# Mini-RS485_RJ45-GW-v01.net
KiCad netlist of a schematic drawn in EAGLE
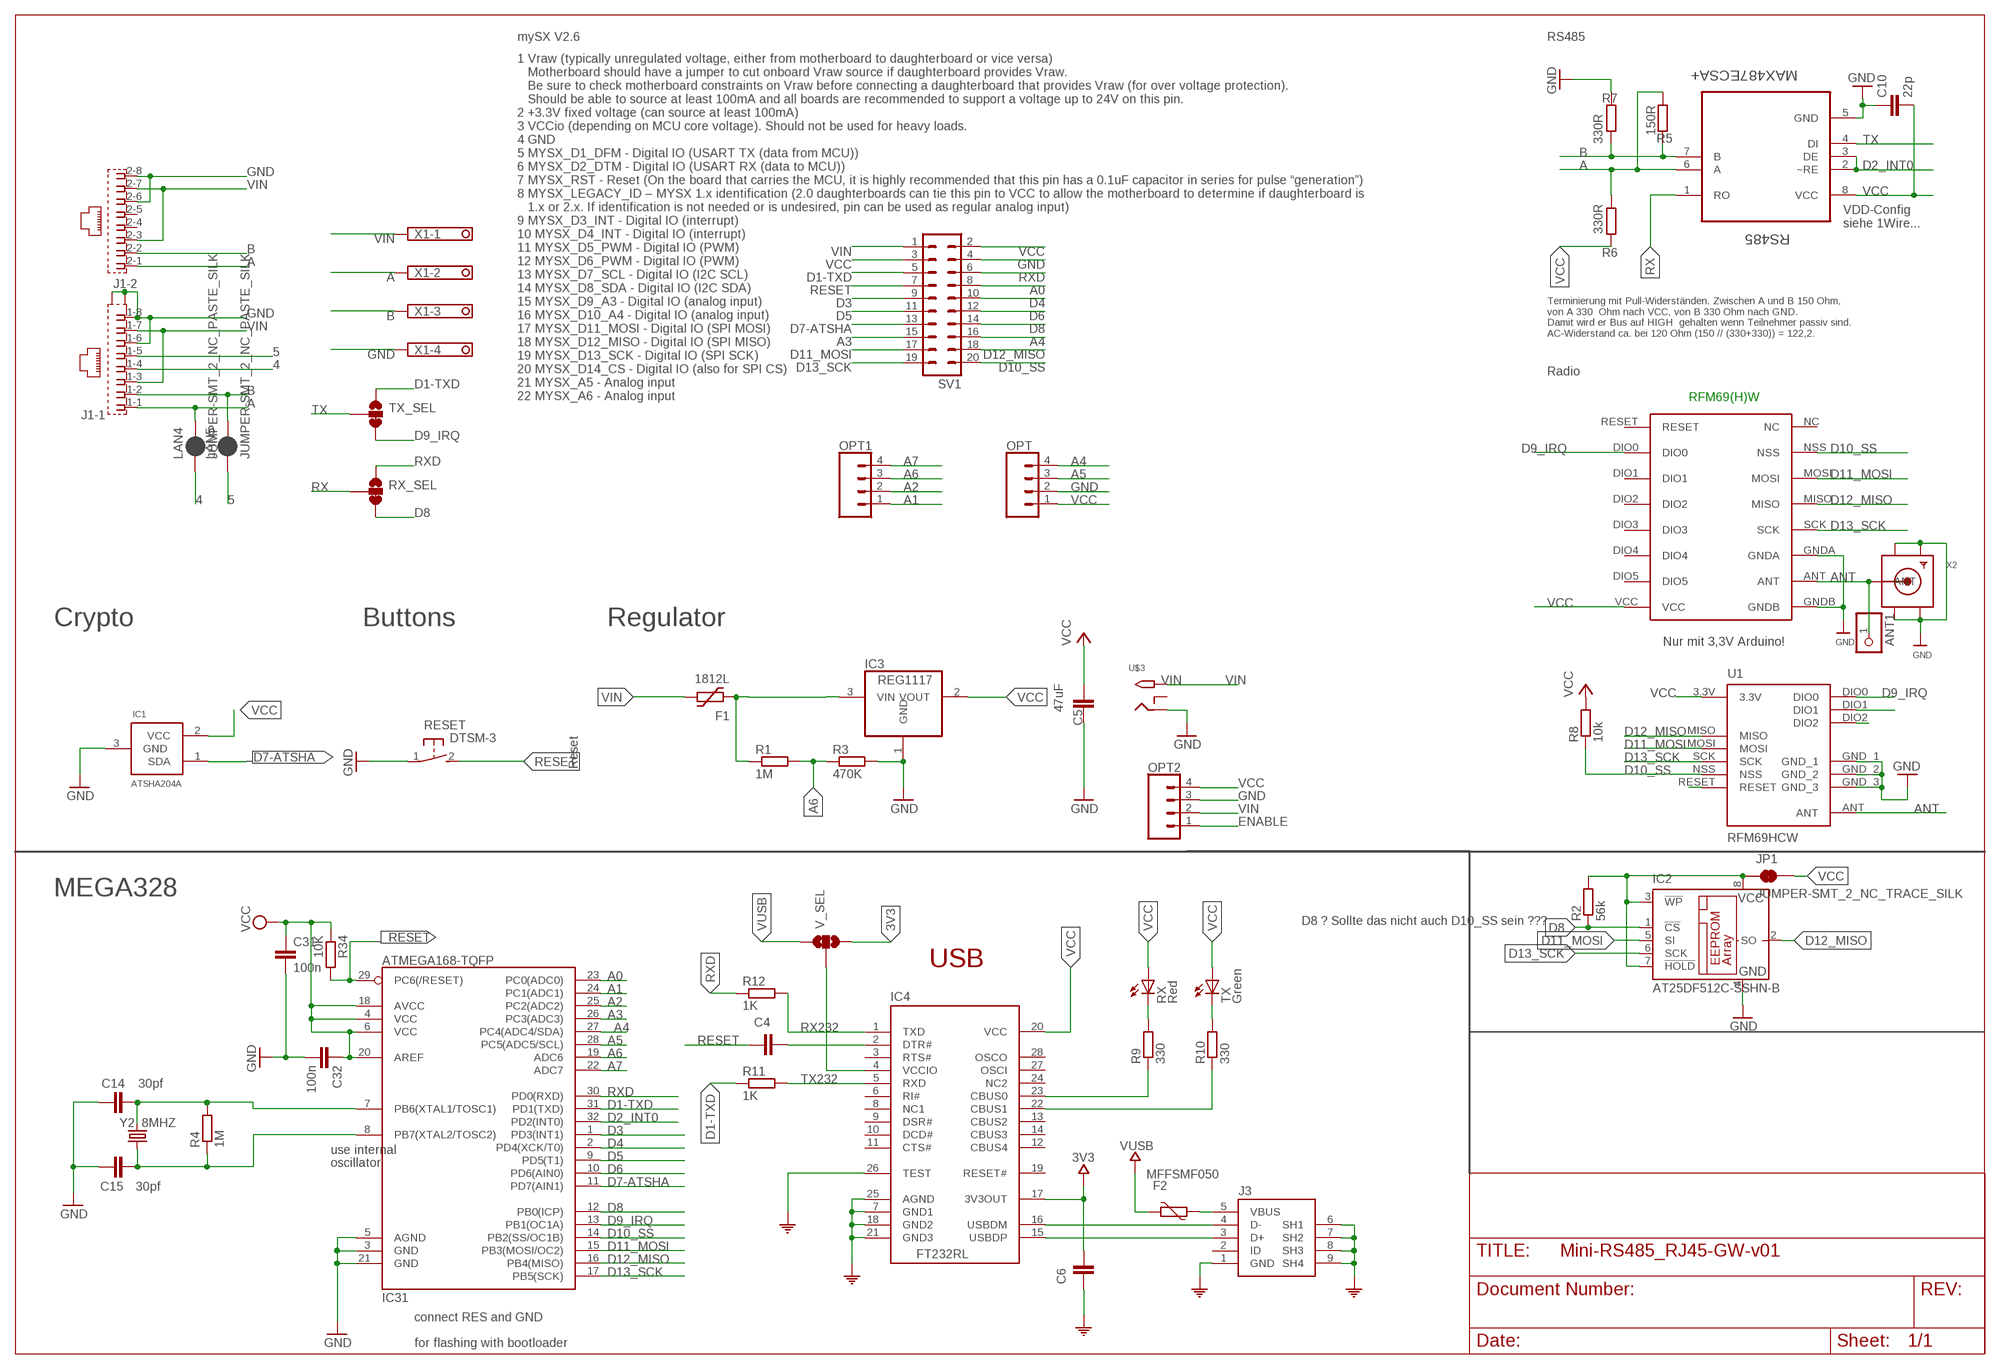
[diagram p0: schematic, sheet 1]

(export (version "E")
  (design (tool "Eeschema 10.0.6"))
  (components
    (comp (ref "ANT1")
      (value "PINHD-1X1")
      (footprint "eagle-import:1X01")
      (libsource (lib "eagle-import") (part "PINHD-1X1"))
    )
    (comp (ref "C4")
      (value "100nF")
      (footprint "eagle-import:C0805")
      (libsource (lib "eagle-import") (part "resistor_348_C-EUC0805"))
    )
    (comp (ref "C5")
      (value "47uF")
      (footprint "eagle-import:C1210")
      (libsource (lib "eagle-import") (part "C-EUC1210"))
    )
    (comp (ref "C6")
      (value "100nF")
      (footprint "eagle-import:C0805")
      (libsource (lib "eagle-import") (part "resistor_348_C-EUC0805"))
    )
    (comp (ref "C10")
      (value "22p")
      (footprint "eagle-import:C0805")
      (libsource (lib "eagle-import") (part "C-EUC0805"))
    )
    (comp (ref "C14")
      (value "30pf")
      (footprint "eagle-import:0805")
      (libsource (lib "eagle-import") (part "CAP0805"))
    )
    (comp (ref "C15")
      (value "30pf")
      (footprint "eagle-import:0805")
      (libsource (lib "eagle-import") (part "CAP0805"))
    )
    (comp (ref "C31")
      (value "100n")
      (footprint "eagle-import:C0805")
      (libsource (lib "eagle-import") (part "C-EUC0805"))
    )
    (comp (ref "C32")
      (value "100n")
      (footprint "eagle-import:C0805")
      (libsource (lib "eagle-import") (part "C-EUC0805"))
    )
    (comp (ref "F1")
      (value "1812L")
      (footprint "eagle-import:1812L")
      (libsource (lib "eagle-import") (part "1812L"))
    )
    (comp (ref "F2")
      (value "MFFSMF050")
      (footprint "eagle-import:0603-1608X90N")
      (fields (field (name "MANUFACTURER") "Bourns Inc "))
      (libsource (lib "eagle-import") (part "PTC"))
    )
    (comp (ref "IC1")
      (value "ATSHA204A")
      (footprint "eagle-import:SOT23")
      (libsource (lib "eagle-import") (part "ATSHA204A"))
    )
    (comp (ref "IC2")
      (value "AT25DF512C-SSHN-B")
      (footprint "eagle-import:SO-08")
      (fields (field (name "MF") "MICROCHIP") (field (name "MPN") "25AA080/SN"))
      (libsource (lib "eagle-import") (part "25SNAA080"))
    )
    (comp (ref "IC3")
      (value "REG1117")
      (footprint "eagle-import:SOT223")
      (libsource (lib "eagle-import") (part "REG1117"))
    )
    (comp (ref "IC4")
      (value "FT232RL")
      (footprint "eagle-import:SSOP28")
      (libsource (lib "eagle-import") (part "0226_FT232RL"))
    )
    (comp (ref "IC31")
      (value "ATMEGA168-TQFP")
      (footprint "eagle-import:TQFP32-08")
      (libsource (lib "eagle-import") (part "ATMEGA168-TQFP"))
    )
    (comp (ref "J1")
      (value "RJ45_2X_NARROW_SHILDPINS")
      (footprint "eagle-import:RJ45_2X_NARROW_SHILDPINS")
      (libsource (lib "eagle-import") (part "RJ45_2X_NARROW_SHILDPINS"))
    )
    (comp (ref "J3")
      (value "0219_14850")
      (footprint "eagle-import:USB-MINI-B_2")
      (fields (field (name "PART_NUMBER") "14850"))
      (libsource (lib "eagle-import") (part "0219_14850"))
    )
    (comp (ref "JP1")
      (value "JUMPER-SMT_2_NC_TRACE_SILK")
      (footprint "eagle-import:SMT-JUMPER_2_NC_TRACE_SILK")
      (libsource (lib "eagle-import") (part "JUMPER-SMT_2_NC_TRACE_SILK"))
    )
    (comp (ref "LAN4")
      (value "JUMPER-SMT_2_NC_PASTE_SILK")
      (footprint "eagle-import:SMT-JUMPER_2_NC_PASTE_SILK")
      (libsource (lib "eagle-import") (part "JUMPER-SMT_2_NC_PASTE_SILK"))
    )
    (comp (ref "LAN5")
      (value "JUMPER-SMT_2_NC_PASTE_SILK")
      (footprint "eagle-import:SMT-JUMPER_2_NC_PASTE_SILK")
      (libsource (lib "eagle-import") (part "JUMPER-SMT_2_NC_PASTE_SILK"))
    )
    (comp (ref "OPT")
      (value "CONN_04")
      (footprint "eagle-import:1X04")
      (libsource (lib "eagle-import") (part "CONN_04"))
    )
    (comp (ref "OPT1")
      (value "CONN_04")
      (footprint "eagle-import:1X04")
      (libsource (lib "eagle-import") (part "CONN_04"))
    )
    (comp (ref "OPT2")
      (value "CONN_04")
      (footprint "eagle-import:1X04")
      (libsource (lib "eagle-import") (part "CONN_04"))
    )
    (comp (ref "R1")
      (value "1M")
      (footprint "eagle-import:M0805")
      (libsource (lib "eagle-import") (part "R-EU_M0805"))
    )
    (comp (ref "R2")
      (value "56k")
      (footprint "eagle-import:M0805")
      (libsource (lib "eagle-import") (part "resistor_R-EU_M0805"))
    )
    (comp (ref "R3")
      (value "470K")
      (footprint "eagle-import:R0805")
      (libsource (lib "eagle-import") (part "R-EU_R0805"))
    )
    (comp (ref "R4")
      (value "1M")
      (footprint "eagle-import:M0805")
      (libsource (lib "eagle-import") (part "R-EU_M0805"))
    )
    (comp (ref "R5")
      (value "150R")
      (footprint "eagle-import:R0805")
      (libsource (lib "eagle-import") (part "R-EU_R0805"))
    )
    (comp (ref "R6")
      (value "330R")
      (footprint "eagle-import:R0805")
      (libsource (lib "eagle-import") (part "R-EU_R0805"))
    )
    (comp (ref "R7")
      (value "330R")
      (footprint "eagle-import:R0805")
      (libsource (lib "eagle-import") (part "R-EU_R0805"))
    )
    (comp (ref "R8")
      (value "10k")
      (footprint "eagle-import:M0805")
      (libsource (lib "eagle-import") (part "R-EU_M0805"))
    )
    (comp (ref "R9")
      (value "330")
      (footprint "eagle-import:R0805")
      (libsource (lib "eagle-import") (part "resistor_348_R-EU_R0805"))
    )
    (comp (ref "R10")
      (value "330")
      (footprint "eagle-import:R0805")
      (libsource (lib "eagle-import") (part "resistor_348_R-EU_R0805"))
    )
    (comp (ref "R11")
      (value "1K")
      (footprint "eagle-import:R0805")
      (libsource (lib "eagle-import") (part "resistor_348_R-EU_R0805"))
    )
    (comp (ref "R12")
      (value "1K")
      (footprint "eagle-import:R0805")
      (libsource (lib "eagle-import") (part "resistor_348_R-EU_R0805"))
    )
    (comp (ref "R34")
      (value "10K")
      (footprint "eagle-import:R0805")
      (libsource (lib "eagle-import") (part "R-EU_R0805"))
    )
    (comp (ref "RESET")
      (value "DTSM-3")
      (footprint "eagle-import:DTSM-3")
      (libsource (lib "eagle-import") (part "DTSM-3"))
    )
    (comp (ref "RFM69W")
      (value "RFM69HW")
      (footprint "eagle-import:RFM")
      (libsource (lib "eagle-import") (part "RFM69HW"))
    )
    (comp (ref "RS485")
      (value "MAX487ECSA+")
      (footprint "eagle-import:SOIC127P600X175-8N")
      (libsource (lib "eagle-import") (part "MAX487ECSA+"))
    )
    (comp (ref "RX")
      (value "Red")
      (footprint "eagle-import:CHIPLED_0805")
      (fields (field (name "PART_NUMBER") "KTP-2012SURCK"))
      (libsource (lib "eagle-import") (part "0181_KTP-2012SURCK"))
    )
    (comp (ref "RX_SEL")
      (value "JUMPER-SMT_3_1-NC_TRACE_SILK")
      (footprint "eagle-import:SMT-JUMPER_3_1-NC_TRACE_SILK")
      (libsource (lib "eagle-import") (part "JUMPER-SMT_3_1-NC_TRACE_SILK"))
    )
    (comp (ref "SV1")
      (value "MA10-2")
      (footprint "eagle-import:MA10-2")
      (libsource (lib "eagle-import") (part "MA10-2"))
    )
    (comp (ref "TX")
      (value "Green")
      (footprint "eagle-import:CHIPLED_0805")
      (fields (field (name "PART_NUMBER") "KPT-2012SGC"))
      (libsource (lib "eagle-import") (part "0043_KPT-2012SGC"))
    )
    (comp (ref "TX_SEL")
      (value "JUMPER-SMT_3_1-NC_TRACE_SILK")
      (footprint "eagle-import:SMT-JUMPER_3_1-NC_TRACE_SILK")
      (libsource (lib "eagle-import") (part "JUMPER-SMT_3_1-NC_TRACE_SILK"))
    )
    (comp (ref "U$3")
      (value "2.1MMJACKTHM")
      (footprint "eagle-import:PJ-102A")
      (libsource (lib "eagle-import") (part "2.1MMJACKTHM"))
    )
    (comp (ref "U1")
      (value "RFM69HCW")
      (footprint "eagle-import:RFM69HCW-XXXS2")
      (libsource (lib "eagle-import") (part "RFM69HCW"))
    )
    (comp (ref "V_SEL")
      (value "JUMPER-SMT_3_NO_SILK")
      (footprint "eagle-import:SMT-JUMPER_3_NO_SILK")
      (libsource (lib "eagle-import") (part "JUMPER-SMT_3_NO_SILK"))
    )
    (comp (ref "X1")
      (value "1751264")
      (footprint "eagle-import:1751264")
      (libsource (lib "eagle-import") (part "1751264"))
    )
    (comp (ref "X2")
      (value "SMACONNECTOR_EDGE")
      (footprint "eagle-import:SMA_EDGELAUNCH")
      (libsource (lib "eagle-import") (part "SMACONNECTOR_EDGE"))
    )
    (comp (ref "Y2")
      (value "8MHZ")
      (footprint "eagle-import:CRYSTAL-TXC-7A")
      (libsource (lib "eagle-import") (part "CRYSTALTXC-7A"))
    )
  )
  (nets
    (net (code "1") (name "/4") (class "Default")
      (node (ref "J1") (pin "1-4") (pinfunction "4_1-4") (pintype "passive"))
      (node (ref "LAN4") (pin "1") (pinfunction "1_1") (pintype "passive"))
    )
    (net (code "2") (name "/5") (class "Default")
      (node (ref "J1") (pin "1-5") (pinfunction "5_1-5") (pintype "passive"))
      (node (ref "LAN5") (pin "1") (pinfunction "1_1") (pintype "passive"))
    )
    (net (code "3") (name "/A") (class "Default")
      (node (ref "J1") (pin "1-1") (pinfunction "1_1-1") (pintype "passive"))
      (node (ref "J1") (pin "2-1") (pinfunction "1_2-1") (pintype "passive"))
      (node (ref "LAN4") (pin "2") (pinfunction "2_2") (pintype "passive"))
      (node (ref "R5") (pin "1") (pinfunction "1_1") (pintype "passive"))
      (node (ref "R6") (pin "2") (pinfunction "2_2") (pintype "passive"))
      (node (ref "RS485") (pin "6") (pinfunction "A_6") (pintype "bidirectional"))
      (node (ref "X1") (pin "2") (pinfunction "K_2") (pintype "passive"))
    )
    (net (code "4") (name "/A0") (class "Default")
      (node (ref "IC31") (pin "23") (pinfunction "PC0(ADC0)_23") (pintype "bidirectional"))
      (node (ref "SV1") (pin "8") (pinfunction "8_8") (pintype "passive"))
    )
    (net (code "5") (name "/A1") (class "Default")
      (node (ref "IC31") (pin "24") (pinfunction "PC1(ADC1)_24") (pintype "bidirectional"))
      (node (ref "OPT1") (pin "1") (pinfunction "1_1") (pintype "passive"))
    )
    (net (code "6") (name "/A2") (class "Default")
      (node (ref "IC31") (pin "25") (pinfunction "PC2(ADC2)_25") (pintype "bidirectional"))
      (node (ref "OPT1") (pin "2") (pinfunction "2_2") (pintype "passive"))
    )
    (net (code "7") (name "/A3") (class "Default")
      (node (ref "IC31") (pin "26") (pinfunction "PC3(ADC3)_26") (pintype "bidirectional"))
      (node (ref "SV1") (pin "15") (pinfunction "15_15") (pintype "passive"))
    )
    (net (code "8") (name "/A4") (class "Default")
      (node (ref "IC31") (pin "27") (pinfunction "PC4(ADC4/SDA)_27") (pintype "bidirectional"))
      (node (ref "OPT") (pin "4") (pinfunction "4_4") (pintype "passive"))
      (node (ref "SV1") (pin "16") (pinfunction "16_16") (pintype "passive"))
    )
    (net (code "9") (name "/A5") (class "Default")
      (node (ref "IC31") (pin "28") (pinfunction "PC5(ADC5/SCL)_28") (pintype "bidirectional"))
      (node (ref "OPT") (pin "3") (pinfunction "3_3") (pintype "passive"))
    )
    (net (code "10") (name "/A7") (class "Default")
      (node (ref "IC31") (pin "22") (pinfunction "ADC7_22") (pintype "bidirectional"))
      (node (ref "OPT1") (pin "4") (pinfunction "4_4") (pintype "passive"))
    )
    (net (code "11") (name "/ANT") (class "Default")
      (node (ref "ANT1") (pin "1") (pinfunction "1_1") (pintype "passive"))
      (node (ref "RFM69W") (pin "ANT") (pinfunction "ANT_ANT") (pintype "bidirectional"))
      (node (ref "U1") (pin "ANT") (pinfunction "ANT_ANT") (pintype "passive"))
      (node (ref "X2") (pin "P") (pinfunction "ANT_P") (pintype "bidirectional"))
    )
    (net (code "12") (name "/B") (class "Default")
      (node (ref "J1") (pin "1-2") (pinfunction "2_1-2") (pintype "passive"))
      (node (ref "J1") (pin "2-2") (pinfunction "2_2-2") (pintype "passive"))
      (node (ref "LAN5") (pin "2") (pinfunction "2_2") (pintype "passive"))
      (node (ref "R5") (pin "2") (pinfunction "2_2") (pintype "passive"))
      (node (ref "R7") (pin "1") (pinfunction "1_1") (pintype "passive"))
      (node (ref "RS485") (pin "7") (pinfunction "B_7") (pintype "bidirectional"))
      (node (ref "X1") (pin "3") (pinfunction "K_3") (pintype "passive"))
    )
    (net (code "13") (name "/D2_INT0") (class "Default")
      (node (ref "IC31") (pin "32") (pinfunction "PD2(INT0)_32") (pintype "bidirectional"))
      (node (ref "RS485") (pin "2") (pinfunction "~{RE}_2") (pintype "input"))
      (node (ref "RS485") (pin "3") (pinfunction "DE_3") (pintype "input"))
    )
    (net (code "14") (name "/D3") (class "Default")
      (node (ref "IC31") (pin "1") (pinfunction "PD3(INT1)_1") (pintype "bidirectional"))
      (node (ref "SV1") (pin "9") (pinfunction "9_9") (pintype "passive"))
    )
    (net (code "15") (name "/D4") (class "Default")
      (node (ref "IC31") (pin "2") (pinfunction "PD4(XCK/T0)_2") (pintype "bidirectional"))
      (node (ref "SV1") (pin "10") (pinfunction "10_10") (pintype "passive"))
    )
    (net (code "16") (name "/D5") (class "Default")
      (node (ref "IC31") (pin "9") (pinfunction "PD5(T1)_9") (pintype "bidirectional"))
      (node (ref "SV1") (pin "11") (pinfunction "11_11") (pintype "passive"))
    )
    (net (code "17") (name "/D6") (class "Default")
      (node (ref "IC31") (pin "10") (pinfunction "PD6(AIN0)_10") (pintype "bidirectional"))
      (node (ref "SV1") (pin "12") (pinfunction "12_12") (pintype "passive"))
    )
    (net (code "18") (name "/D7-ATSHA") (class "Default")
      (node (ref "IC1") (pin "1") (pinfunction "SDA_1") (pintype "bidirectional"))
      (node (ref "IC31") (pin "11") (pinfunction "PD7(AIN1)_11") (pintype "bidirectional"))
      (node (ref "SV1") (pin "13") (pinfunction "13_13") (pintype "passive"))
    )
    (net (code "19") (name "/D9_IRQ") (class "Default")
      (node (ref "IC31") (pin "13") (pinfunction "PB1(OC1A)_13") (pintype "bidirectional"))
      (node (ref "RFM69W") (pin "DIO0") (pinfunction "DIO0_DIO0") (pintype "bidirectional"))
      (node (ref "TX_SEL") (pin "3") (pinfunction "3_3") (pintype "passive"))
      (node (ref "U1") (pin "DIO0") (pinfunction "DIO0_DIO0") (pintype "bidirectional"))
    )
    (net (code "20") (name "/D10_SS") (class "Default")
      (node (ref "IC31") (pin "14") (pinfunction "PB2(SS/OC1B)_14") (pintype "bidirectional"))
      (node (ref "R8") (pin "1") (pinfunction "1_1") (pintype "passive"))
      (node (ref "RFM69W") (pin "NSS") (pinfunction "NSS_NSS") (pintype "bidirectional"))
      (node (ref "SV1") (pin "20") (pinfunction "20_20") (pintype "passive"))
      (node (ref "U1") (pin "NSS") (pinfunction "NSS_NSS") (pintype "input"))
    )
    (net (code "21") (name "/ENABLE") (class "Default")
      (node (ref "OPT2") (pin "1") (pinfunction "1_1") (pintype "passive"))
    )
    (net (code "22") (name "/RX232") (class "Default")
      (node (ref "IC4") (pin "1") (pinfunction "TXD_1") (pintype "output"))
      (node (ref "R12") (pin "2") (pinfunction "2_2") (pintype "passive"))
    )
    (net (code "23") (name "/TX") (class "Default")
      (node (ref "RS485") (pin "4") (pinfunction "DI_4") (pintype "input"))
      (node (ref "TX_SEL") (pin "2") (pinfunction "2_2") (pintype "passive"))
    )
    (net (code "24") (name "/TX232") (class "Default")
      (node (ref "IC4") (pin "5") (pinfunction "RXD_5") (pintype "input"))
      (node (ref "R11") (pin "2") (pinfunction "2_2") (pintype "passive"))
    )
    (net (code "25") (name "3V3") (class "Default")
      (node (ref "C6") (pin "2") (pinfunction "2_2") (pintype "passive"))
      (node (ref "IC4") (pin "17") (pinfunction "3V3OUT_17") (pintype "power_in"))
      (node (ref "V_SEL") (pin "3") (pinfunction "3_3") (pintype "passive"))
    )
    (net (code "26") (name "A6") (class "Default")
      (node (ref "IC31") (pin "19") (pinfunction "ADC6_19") (pintype "bidirectional"))
      (node (ref "OPT1") (pin "3") (pinfunction "3_3") (pintype "passive"))
      (node (ref "R1") (pin "2") (pinfunction "2_2") (pintype "passive"))
      (node (ref "R3") (pin "1") (pinfunction "1_1") (pintype "passive"))
    )
    (net (code "27") (name "COM") (class "Default")
      (node (ref "C6") (pin "1") (pinfunction "1_1") (pintype "passive"))
      (node (ref "IC4") (pin "18") (pinfunction "GND2_18") (pintype "power_in"))
      (node (ref "IC4") (pin "21") (pinfunction "GND3_21") (pintype "power_in"))
      (node (ref "IC4") (pin "25") (pinfunction "AGND_25") (pintype "power_in"))
      (node (ref "IC4") (pin "26") (pinfunction "TEST_26") (pintype "bidirectional"))
      (node (ref "IC4") (pin "7") (pinfunction "GND1_7") (pintype "power_in"))
      (node (ref "J3") (pin "1") (pinfunction "GND_1") (pintype "passive"))
      (node (ref "J3") (pin "6") (pinfunction "SH1_6") (pintype "passive"))
      (node (ref "J3") (pin "7") (pinfunction "SH2_7") (pintype "passive"))
      (node (ref "J3") (pin "8") (pinfunction "SH3_8") (pintype "passive"))
      (node (ref "J3") (pin "9") (pinfunction "SH4_9") (pintype "passive"))
    )
    (net (code "28") (name "D1-TXD") (class "Default")
      (node (ref "IC31") (pin "31") (pinfunction "PD1(TXD)_31") (pintype "bidirectional"))
      (node (ref "R11") (pin "1") (pinfunction "1_1") (pintype "passive"))
      (node (ref "SV1") (pin "5") (pinfunction "5_5") (pintype "passive"))
      (node (ref "TX_SEL") (pin "1") (pinfunction "1_1") (pintype "passive"))
    )
    (net (code "29") (name "D8") (class "Default")
      (node (ref "IC2") (pin "1") (pinfunction "~{CS}_1") (pintype "input"))
      (node (ref "IC31") (pin "12") (pinfunction "PB0(ICP)_12") (pintype "bidirectional"))
      (node (ref "R2") (pin "1") (pinfunction "1_1") (pintype "passive"))
      (node (ref "RX_SEL") (pin "3") (pinfunction "3_3") (pintype "passive"))
      (node (ref "SV1") (pin "14") (pinfunction "14_14") (pintype "passive"))
    )
    (net (code "30") (name "D11_MOSI") (class "Default")
      (node (ref "IC2") (pin "5") (pinfunction "SI_5") (pintype "input"))
      (node (ref "IC31") (pin "15") (pinfunction "PB3(MOSI/OC2)_15") (pintype "bidirectional"))
      (node (ref "RFM69W") (pin "MOSI") (pinfunction "MOSI_MOSI") (pintype "bidirectional"))
      (node (ref "SV1") (pin "17") (pinfunction "17_17") (pintype "passive"))
      (node (ref "U1") (pin "MOSI") (pinfunction "MOSI_MOSI") (pintype "input"))
    )
    (net (code "31") (name "D12_MISO") (class "Default")
      (node (ref "IC2") (pin "2") (pinfunction "SO_2") (pintype "bidirectional"))
      (node (ref "IC31") (pin "16") (pinfunction "PB4(MISO)_16") (pintype "bidirectional"))
      (node (ref "RFM69W") (pin "MISO") (pinfunction "MISO_MISO") (pintype "bidirectional"))
      (node (ref "SV1") (pin "18") (pinfunction "18_18") (pintype "passive"))
      (node (ref "U1") (pin "MISO") (pinfunction "MISO_MISO") (pintype "bidirectional"))
    )
    (net (code "32") (name "D13_SCK") (class "Default")
      (node (ref "IC2") (pin "6") (pinfunction "SCK_6") (pintype "input"))
      (node (ref "IC31") (pin "17") (pinfunction "PB5(SCK)_17") (pintype "bidirectional"))
      (node (ref "RFM69W") (pin "SCK") (pinfunction "SCK_SCK") (pintype "bidirectional"))
      (node (ref "SV1") (pin "19") (pinfunction "19_19") (pintype "passive"))
      (node (ref "U1") (pin "SCK") (pinfunction "SCK_SCK") (pintype "input"))
    )
    (net (code "33") (name "GND") (class "Default")
      (node (ref "C10") (pin "1") (pinfunction "1_1") (pintype "passive"))
      (node (ref "C14") (pin "1") (pinfunction "1_1") (pintype "passive"))
      (node (ref "C15") (pin "1") (pinfunction "1_1") (pintype "passive"))
      (node (ref "C31") (pin "2") (pinfunction "2_2") (pintype "passive"))
      (node (ref "C32") (pin "2") (pinfunction "2_2") (pintype "passive"))
      (node (ref "C5") (pin "1") (pinfunction "1_1") (pintype "passive"))
      (node (ref "IC1") (pin "3") (pinfunction "GND_3") (pintype "bidirectional"))
      (node (ref "IC2") (pin "4") (pinfunction "GND_4") (pintype "power_in"))
      (node (ref "IC3") (pin "1") (pinfunction "GND_1") (pintype "power_in"))
      (node (ref "IC31") (pin "21") (pinfunction "GND_21") (pintype "bidirectional"))
      (node (ref "IC31") (pin "3") (pinfunction "GND_3") (pintype "bidirectional"))
      (node (ref "IC31") (pin "5") (pinfunction "AGND_5") (pintype "bidirectional"))
      (node (ref "J1") (pin "1-6") (pinfunction "6_1-6") (pintype "passive"))
      (node (ref "J1") (pin "1-8") (pinfunction "8_1-8") (pintype "passive"))
      (node (ref "J1") (pin "2-6") (pinfunction "6_2-6") (pintype "passive"))
      (node (ref "J1") (pin "2-8") (pinfunction "8_2-8") (pintype "passive"))
      (node (ref "J1") (pin "G1") (pinfunction "S1_G1") (pintype "passive"))
      (node (ref "J1") (pin "G3") (pinfunction "S2_G3") (pintype "passive"))
      (node (ref "OPT") (pin "2") (pinfunction "2_2") (pintype "passive"))
      (node (ref "OPT2") (pin "3") (pinfunction "3_3") (pintype "passive"))
      (node (ref "R3") (pin "2") (pinfunction "2_2") (pintype "passive"))
      (node (ref "R7") (pin "2") (pinfunction "2_2") (pintype "passive"))
      (node (ref "RESET") (pin "1") (pinfunction "1_1") (pintype "passive"))
      (node (ref "RFM69W") (pin "GNDA") (pinfunction "GNDA_GNDA") (pintype "bidirectional"))
      (node (ref "RFM69W") (pin "GNDB") (pinfunction "GNDB_GNDB") (pintype "bidirectional"))
      (node (ref "RS485") (pin "5") (pinfunction "GND_5") (pintype "passive"))
      (node (ref "SV1") (pin "4") (pinfunction "4_4") (pintype "passive"))
      (node (ref "U$3") (pin "RING") (pinfunction "RING_RING") (pintype "bidirectional"))
      (node (ref "U1") (pin "GND_1") (pinfunction "GND_1_GND_1") (pintype "power_in"))
      (node (ref "U1") (pin "GND_2") (pinfunction "GND_2_GND_2") (pintype "power_in"))
      (node (ref "U1") (pin "GND_3") (pinfunction "GND_3_GND_3") (pintype "power_in"))
      (node (ref "X1") (pin "4") (pinfunction "K_4") (pintype "passive"))
      (node (ref "X2") (pin "GND@1") (pinfunction "GND4_GND@1") (pintype "power_in"))
      (node (ref "X2") (pin "GND@2") (pinfunction "GND3_GND@2") (pintype "power_in"))
      (node (ref "X2") (pin "GND@3") (pinfunction "GND2_GND@3") (pintype "power_in"))
      (node (ref "X2") (pin "GND@4") (pinfunction "GND1_GND@4") (pintype "power_in"))
    )
    (net (code "34") (name "Net-(F1-1)") (class "Default")
      (node (ref "F1") (pin "P$1") (pinfunction "1_P$1") (pintype "passive"))
      (node (ref "IC3") (pin "3") (pinfunction "VIN_3") (pintype "input"))
      (node (ref "R1") (pin "1") (pinfunction "1_1") (pintype "passive"))
    )
    (net (code "35") (name "Net-(IC2-VCC)") (class "Default")
      (node (ref "IC2") (pin "3") (pinfunction "~{WP}_3") (pintype "input"))
      (node (ref "IC2") (pin "7") (pinfunction "~{HOLD}_7") (pintype "input"))
      (node (ref "IC2") (pin "8") (pinfunction "VCC_8") (pintype "power_in"))
      (node (ref "JP1") (pin "1") (pinfunction "1_1") (pintype "passive"))
      (node (ref "R2") (pin "2") (pinfunction "2_2") (pintype "passive"))
    )
    (net (code "36") (name "Net-(IC4-CBUS0)") (class "Default")
      (node (ref "IC4") (pin "23") (pinfunction "CBUS0_23") (pintype "bidirectional"))
      (node (ref "R9") (pin "1") (pinfunction "1_1") (pintype "passive"))
    )
    (net (code "37") (name "Net-(IC4-CBUS1)") (class "Default")
      (node (ref "IC4") (pin "22") (pinfunction "CBUS1_22") (pintype "bidirectional"))
      (node (ref "R10") (pin "1") (pinfunction "1_1") (pintype "passive"))
    )
    (net (code "38") (name "Net-(IC4-DTR#)") (class "Default")
      (node (ref "C4") (pin "2") (pinfunction "2_2") (pintype "passive"))
      (node (ref "IC4") (pin "2") (pinfunction "DTR#_2") (pintype "output"))
    )
    (net (code "39") (name "Net-(IC4-USBDM)") (class "Default")
      (node (ref "IC4") (pin "16") (pinfunction "USBDM_16") (pintype "bidirectional"))
      (node (ref "J3") (pin "4") (pinfunction "D-_4") (pintype "bidirectional"))
    )
    (net (code "40") (name "Net-(IC4-USBDP)") (class "Default")
      (node (ref "IC4") (pin "15") (pinfunction "USBDP_15") (pintype "bidirectional"))
      (node (ref "J3") (pin "3") (pinfunction "D+_3") (pintype "bidirectional"))
    )
    (net (code "41") (name "Net-(IC4-VCCIO)") (class "Default")
      (node (ref "IC4") (pin "4") (pinfunction "VCCIO_4") (pintype "power_in"))
      (node (ref "V_SEL") (pin "2") (pinfunction "2_2") (pintype "passive"))
    )
    (net (code "42") (name "Net-(IC31-PB6(XTAL1{slash}TOSC1))") (class "Default")
      (node (ref "C14") (pin "2") (pinfunction "2_2") (pintype "passive"))
      (node (ref "IC31") (pin "7") (pinfunction "PB6(XTAL1/TOSC1)_7") (pintype "bidirectional"))
      (node (ref "R4") (pin "2") (pinfunction "2_2") (pintype "passive"))
      (node (ref "Y2") (pin "P$2") (pinfunction "2_P$2") (pintype "passive"))
    )
    (net (code "43") (name "Net-(IC31-PB7(XTAL2{slash}TOSC2))") (class "Default")
      (node (ref "C15") (pin "2") (pinfunction "2_2") (pintype "passive"))
      (node (ref "IC31") (pin "8") (pinfunction "PB7(XTAL2/TOSC2)_8") (pintype "bidirectional"))
      (node (ref "R4") (pin "1") (pinfunction "1_1") (pintype "passive"))
      (node (ref "Y2") (pin "P$1") (pinfunction "1_P$1") (pintype "passive"))
    )
    (net (code "44") (name "Net-(J3-VBUS)") (class "Default")
      (node (ref "F2") (pin "2") (pinfunction "2_2") (pintype "passive"))
      (node (ref "J3") (pin "5") (pinfunction "VBUS_5") (pintype "power_in"))
    )
    (net (code "45") (name "Net-(R9-Pad2)") (class "Default")
      (node (ref "R9") (pin "2") (pinfunction "2_2") (pintype "passive"))
      (node (ref "RX") (pin "C") (pinfunction "C_C") (pintype "passive"))
    )
    (net (code "46") (name "Net-(R10-Pad2)") (class "Default")
      (node (ref "R10") (pin "2") (pinfunction "2_2") (pintype "passive"))
      (node (ref "TX") (pin "C") (pinfunction "C_C") (pintype "passive"))
    )
    (net (code "47") (name "RESET") (class "Default")
      (node (ref "C4") (pin "1") (pinfunction "1_1") (pintype "passive"))
      (node (ref "IC31") (pin "29") (pinfunction "PC6(/RESET)_29") (pintype "bidirectional"))
      (node (ref "R34") (pin "2") (pinfunction "2_2") (pintype "passive"))
      (node (ref "RESET") (pin "2") (pinfunction "2_2") (pintype "passive"))
      (node (ref "SV1") (pin "7") (pinfunction "7_7") (pintype "passive"))
    )
    (net (code "48") (name "RX") (class "Default")
      (node (ref "RS485") (pin "1") (pinfunction "RO_1") (pintype "output"))
      (node (ref "RX_SEL") (pin "2") (pinfunction "2_2") (pintype "passive"))
    )
    (net (code "49") (name "RXD") (class "Default")
      (node (ref "IC31") (pin "30") (pinfunction "PD0(RXD)_30") (pintype "bidirectional"))
      (node (ref "R12") (pin "1") (pinfunction "1_1") (pintype "passive"))
      (node (ref "RX_SEL") (pin "1") (pinfunction "1_1") (pintype "passive"))
      (node (ref "SV1") (pin "6") (pinfunction "6_6") (pintype "passive"))
    )
    (net (code "50") (name "VCC") (class "Default")
      (node (ref "C10") (pin "2") (pinfunction "2_2") (pintype "passive"))
      (node (ref "C31") (pin "1") (pinfunction "1_1") (pintype "passive"))
      (node (ref "C32") (pin "1") (pinfunction "1_1") (pintype "passive"))
      (node (ref "C5") (pin "2") (pinfunction "2_2") (pintype "passive"))
      (node (ref "IC1") (pin "2") (pinfunction "VCC_2") (pintype "bidirectional"))
      (node (ref "IC3") (pin "2") (pinfunction "VOUT_2") (pintype "output"))
      (node (ref "IC31") (pin "18") (pinfunction "AVCC_18") (pintype "bidirectional"))
      (node (ref "IC31") (pin "20") (pinfunction "AREF_20") (pintype "bidirectional"))
      (node (ref "IC31") (pin "4") (pinfunction "VCC_4") (pintype "bidirectional"))
      (node (ref "IC31") (pin "6") (pinfunction "VCC_6") (pintype "bidirectional"))
      (node (ref "IC4") (pin "20") (pinfunction "VCC_20") (pintype "power_in"))
      (node (ref "JP1") (pin "2") (pinfunction "2_2") (pintype "passive"))
      (node (ref "OPT") (pin "1") (pinfunction "1_1") (pintype "passive"))
      (node (ref "OPT2") (pin "4") (pinfunction "4_4") (pintype "passive"))
      (node (ref "R34") (pin "1") (pinfunction "1_1") (pintype "passive"))
      (node (ref "R6") (pin "1") (pinfunction "1_1") (pintype "passive"))
      (node (ref "R8") (pin "2") (pinfunction "2_2") (pintype "passive"))
      (node (ref "RFM69W") (pin "VCC") (pinfunction "VCC_VCC") (pintype "bidirectional"))
      (node (ref "RS485") (pin "8") (pinfunction "VCC_8") (pintype "power_in"))
      (node (ref "RX") (pin "A") (pinfunction "A_A") (pintype "passive"))
      (node (ref "SV1") (pin "2") (pinfunction "2_2") (pintype "passive"))
      (node (ref "SV1") (pin "3") (pinfunction "3_3") (pintype "passive"))
      (node (ref "TX") (pin "A") (pinfunction "A_A") (pintype "passive"))
      (node (ref "U1") (pin "3.3V") (pinfunction "3.3V_3.3V") (pintype "power_in"))
    )
    (net (code "51") (name "VIN") (class "Default")
      (node (ref "F1") (pin "P$2") (pinfunction "2_P$2") (pintype "passive"))
      (node (ref "J1") (pin "1-3") (pinfunction "3_1-3") (pintype "passive"))
      (node (ref "J1") (pin "1-7") (pinfunction "7_1-7") (pintype "passive"))
      (node (ref "J1") (pin "2-3") (pinfunction "3_2-3") (pintype "passive"))
      (node (ref "J1") (pin "2-7") (pinfunction "7_2-7") (pintype "passive"))
      (node (ref "OPT2") (pin "2") (pinfunction "2_2") (pintype "passive"))
      (node (ref "SV1") (pin "1") (pinfunction "1_1") (pintype "passive"))
      (node (ref "U$3") (pin "TIP") (pinfunction "TIP_TIP") (pintype "bidirectional"))
      (node (ref "X1") (pin "1") (pinfunction "K_1") (pintype "passive"))
    )
    (net (code "52") (name "VUSB") (class "Default")
      (node (ref "F2") (pin "1") (pinfunction "1_1") (pintype "passive"))
      (node (ref "V_SEL") (pin "1") (pinfunction "1_1") (pintype "passive"))
    )
    (net (code "53") (name "unconnected-(IC4-CBUS2-Pad13)") (class "Default")
      (node (ref "IC4") (pin "13") (pinfunction "CBUS2_13") (pintype "bidirectional"))
    )
    (net (code "54") (name "unconnected-(IC4-CBUS3-Pad14)") (class "Default")
      (node (ref "IC4") (pin "14") (pinfunction "CBUS3_14") (pintype "bidirectional"))
    )
    (net (code "55") (name "unconnected-(IC4-CBUS4-Pad12)") (class "Default")
      (node (ref "IC4") (pin "12") (pinfunction "CBUS4_12") (pintype "bidirectional"))
    )
    (net (code "56") (name "unconnected-(IC4-CTS#-Pad11)") (class "Default")
      (node (ref "IC4") (pin "11") (pinfunction "CTS#_11") (pintype "bidirectional"))
    )
    (net (code "57") (name "unconnected-(IC4-DCD#-Pad10)") (class "Default")
      (node (ref "IC4") (pin "10") (pinfunction "DCD#_10") (pintype "bidirectional"))
    )
    (net (code "58") (name "unconnected-(IC4-DSR#-Pad9)") (class "Default")
      (node (ref "IC4") (pin "9") (pinfunction "DSR#_9") (pintype "bidirectional"))
    )
    (net (code "59") (name "unconnected-(IC4-NC1-Pad8)") (class "Default")
      (node (ref "IC4") (pin "8") (pinfunction "NC1_8") (pintype "bidirectional"))
    )
    (net (code "60") (name "unconnected-(IC4-NC2-Pad24)") (class "Default")
      (node (ref "IC4") (pin "24") (pinfunction "NC2_24") (pintype "no_connect"))
    )
    (net (code "61") (name "unconnected-(IC4-OSCI-Pad27)") (class "Default")
      (node (ref "IC4") (pin "27") (pinfunction "OSCI_27") (pintype "bidirectional"))
    )
    (net (code "62") (name "unconnected-(IC4-OSCO-Pad28)") (class "Default")
      (node (ref "IC4") (pin "28") (pinfunction "OSCO_28") (pintype "output"))
    )
    (net (code "63") (name "unconnected-(IC4-RESET#-Pad19)") (class "Default")
      (node (ref "IC4") (pin "19") (pinfunction "RESET#_19") (pintype "bidirectional"))
    )
    (net (code "64") (name "unconnected-(IC4-RI#-Pad6)") (class "Default")
      (node (ref "IC4") (pin "6") (pinfunction "RI#_6") (pintype "bidirectional"))
    )
    (net (code "65") (name "unconnected-(IC4-RTS#-Pad3)") (class "Default")
      (node (ref "IC4") (pin "3") (pinfunction "RTS#_3") (pintype "output"))
    )
    (net (code "66") (name "unconnected-(J1B-4-Pad2-4)") (class "Default")
      (node (ref "J1") (pin "2-4") (pinfunction "4_2-4") (pintype "passive"))
    )
    (net (code "67") (name "unconnected-(J1B-5-Pad2-5)") (class "Default")
      (node (ref "J1") (pin "2-5") (pinfunction "5_2-5") (pintype "passive"))
    )
    (net (code "68") (name "unconnected-(J3-ID-Pad2)") (class "Default")
      (node (ref "J3") (pin "2") (pinfunction "ID_2") (pintype "bidirectional"))
    )
    (net (code "69") (name "unconnected-(RFM69W-PadDIO1)") (class "Default")
      (node (ref "RFM69W") (pin "DIO1") (pinfunction "DIO1_DIO1") (pintype "bidirectional"))
    )
    (net (code "70") (name "unconnected-(RFM69W-PadDIO2)") (class "Default")
      (node (ref "RFM69W") (pin "DIO2") (pinfunction "DIO2_DIO2") (pintype "bidirectional"))
    )
    (net (code "71") (name "unconnected-(RFM69W-PadDIO3)") (class "Default")
      (node (ref "RFM69W") (pin "DIO3") (pinfunction "DIO3_DIO3") (pintype "bidirectional"))
    )
    (net (code "72") (name "unconnected-(RFM69W-PadDIO4)") (class "Default")
      (node (ref "RFM69W") (pin "DIO4") (pinfunction "DIO4_DIO4") (pintype "bidirectional"))
    )
    (net (code "73") (name "unconnected-(RFM69W-PadDIO5)") (class "Default")
      (node (ref "RFM69W") (pin "DIO5") (pinfunction "DIO5_DIO5") (pintype "bidirectional"))
    )
    (net (code "74") (name "unconnected-(RFM69W-PadNC)") (class "Default")
      (node (ref "RFM69W") (pin "NC") (pinfunction "NC_NC") (pintype "bidirectional"))
    )
    (net (code "75") (name "unconnected-(RFM69W-PadRESET)") (class "Default")
      (node (ref "RFM69W") (pin "RESET") (pinfunction "RESET_RESET") (pintype "bidirectional"))
    )
    (net (code "76") (name "unconnected-(U$3-PadRING_SW)") (class "Default")
      (node (ref "U$3") (pin "RING_SW") (pinfunction "RING_SW_RING_SW") (pintype "bidirectional"))
    )
    (net (code "77") (name "unconnected-(U1-PadDIO1)") (class "Default")
      (node (ref "U1") (pin "DIO1") (pinfunction "DIO1_DIO1") (pintype "bidirectional"))
    )
    (net (code "78") (name "unconnected-(U1-PadDIO2)") (class "Default")
      (node (ref "U1") (pin "DIO2") (pinfunction "DIO2_DIO2") (pintype "bidirectional"))
    )
    (net (code "79") (name "unconnected-(U1-PadRESET)") (class "Default")
      (node (ref "U1") (pin "RESET") (pinfunction "RESET_RESET") (pintype "input"))
    )
  )
)
